# piezo-preamp-tickler_V0-9b.net
KiCad netlist of a schematic drawn in EAGLE
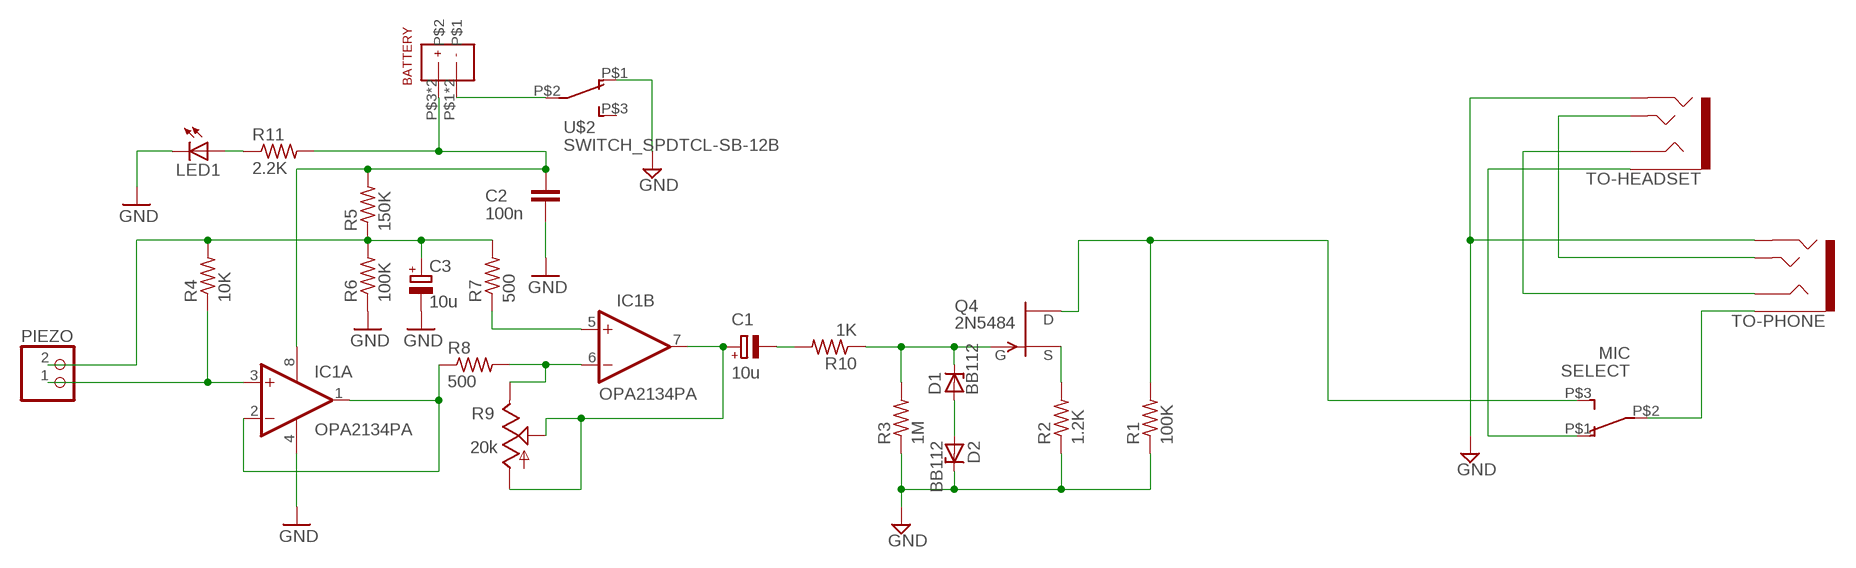
[diagram p0: schematic, sheet 1]

(export (version "E")
  (design (tool "Eeschema 10.0.6"))
  (components
    (comp (ref "BATTERY")
      (value "BATTERY-A27")
      (footprint "eagle-import:BATTERY-A27-KEYSTONE-3651")
      (libsource (lib "eagle-import") (part "BATTERY-A27"))
    )
    (comp (ref "C1")
      (value "10u")
      (footprint "eagle-import:TT2D5L")
      (libsource (lib "eagle-import") (part "CPOL-EUTT2D5L"))
    )
    (comp (ref "C2")
      (value "100n")
      (footprint "eagle-import:C025-025X050")
      (libsource (lib "eagle-import") (part "C-EU025-025X050"))
    )
    (comp (ref "C3")
      (value "10u")
      (footprint "eagle-import:TT2D5L")
      (libsource (lib "eagle-import") (part "CPOL-EUTT2D5L"))
    )
    (comp (ref "D1")
      (value "BB112")
      (footprint "eagle-import:ZDIO-5")
      (libsource (lib "eagle-import") (part "ZENER-DIODEZD-5"))
    )
    (comp (ref "D2")
      (value "BB112")
      (footprint "eagle-import:ZDIO-5")
      (libsource (lib "eagle-import") (part "ZENER-DIODEZD-5"))
    )
    (comp (ref "IC1")
      (value "OPA2134PA")
      (footprint "eagle-import:DIL08")
      (libsource (lib "eagle-import") (part "OPA2PA134"))
    )
    (comp (ref "LED1")
      (value "LED3MM")
      (footprint "eagle-import:LED3MM")
      (libsource (lib "eagle-import") (part "LED3MM"))
    )
    (comp (ref "PIEZO")
      (value "JST_2PIN-THM")
      (footprint "eagle-import:JST-PH-2-THM")
      (libsource (lib "eagle-import") (part "JST_2PIN-THM"))
    )
    (comp (ref "Q4")
      (value "2N5484")
      (footprint "eagle-import:TO92-")
      (libsource (lib "eagle-import") (part "?5482N4"))
    )
    (comp (ref "R1")
      (value "100K")
      (footprint "eagle-import:0204_7")
      (libsource (lib "eagle-import") (part "R-US_0204/7"))
    )
    (comp (ref "R2")
      (value "1.2K")
      (footprint "eagle-import:0204_7")
      (libsource (lib "eagle-import") (part "R-US_0204/7"))
    )
    (comp (ref "R3")
      (value "1M")
      (footprint "eagle-import:0204_7")
      (libsource (lib "eagle-import") (part "R-US_0204/7"))
    )
    (comp (ref "R4")
      (value "10K")
      (footprint "eagle-import:0204_7")
      (libsource (lib "eagle-import") (part "R-US_0204/7"))
    )
    (comp (ref "R5")
      (value "150K")
      (footprint "eagle-import:0204_7")
      (libsource (lib "eagle-import") (part "R-US_0204/7"))
    )
    (comp (ref "R6")
      (value "100K")
      (footprint "eagle-import:0204_7")
      (libsource (lib "eagle-import") (part "R-US_0204/7"))
    )
    (comp (ref "R7")
      (value "500")
      (footprint "eagle-import:0204_7")
      (libsource (lib "eagle-import") (part "R-US_0204/7"))
    )
    (comp (ref "R8")
      (value "500")
      (footprint "eagle-import:0204_7")
      (libsource (lib "eagle-import") (part "R-US_0204/7"))
    )
    (comp (ref "R9")
      (value "20k")
      (footprint "eagle-import:TRIMPOT-BOURNS-3306F")
      (libsource (lib "eagle-import") (part "TRIMPOT-BOURNS"))
    )
    (comp (ref "R10")
      (value "1K")
      (footprint "eagle-import:0204_7")
      (libsource (lib "eagle-import") (part "R-US_0204/7"))
    )
    (comp (ref "R11")
      (value "2.2K")
      (footprint "eagle-import:0204_7")
      (libsource (lib "eagle-import") (part "R-US_0204/7"))
    )
    (comp (ref "SELECT")
      (value "MIC")
      (footprint "eagle-import:SWITCH_SPDT_CL-SB-12B")
      (libsource (lib "eagle-import") (part "SWITCH_SPDTCL-SB-12B"))
    )
    (comp (ref "TO-HEADSET")
      (value "AUDIO-JACK3LGPADS")
      (footprint "eagle-import:AUDIO-JACK-TRRS-SMD")
      (libsource (lib "eagle-import") (part "AUDIO-JACK3LGPADS"))
    )
    (comp (ref "TO-PHONE")
      (value "AUDIO-JACK3LGPADS")
      (footprint "eagle-import:AUDIO-JACK-TRRS-SMD")
      (libsource (lib "eagle-import") (part "AUDIO-JACK3LGPADS"))
    )
    (comp (ref "U$2")
      (value "SWITCH_SPDTCL-SB-12B")
      (footprint "eagle-import:SWITCH_SPDT_CL-SB-12B")
      (libsource (lib "eagle-import") (part "SWITCH_SPDTCL-SB-12B"))
    )
  )
  (nets
    (net (code "1") (name "GND") (class "Default")
      (node (ref "C2") (pin "1") (pinfunction "1_1") (pintype "passive"))
      (node (ref "C3") (pin "-") (pinfunction "-_-") (pintype "passive"))
      (node (ref "D2") (pin "C") (pinfunction "C_C") (pintype "passive"))
      (node (ref "IC1") (pin "4") (pinfunction "V-_4") (pintype "power_in"))
      (node (ref "LED1") (pin "K") (pinfunction "C_K") (pintype "passive"))
      (node (ref "R1") (pin "1") (pinfunction "1_1") (pintype "passive"))
      (node (ref "R2") (pin "1") (pinfunction "1_1") (pintype "passive"))
      (node (ref "R3") (pin "1") (pinfunction "1_1") (pintype "passive"))
      (node (ref "R6") (pin "1") (pinfunction "1_1") (pintype "passive"))
      (node (ref "TO-HEADSET") (pin "RING2") (pinfunction "RING2_RING2") (pintype "bidirectional"))
      (node (ref "TO-PHONE") (pin "RING2") (pinfunction "RING2_RING2") (pintype "bidirectional"))
      (node (ref "U$2") (pin "P$1") (pinfunction "1_P$1") (pintype "passive"))
    )
    (net (code "2") (name "Net-(C1-Pad-)") (class "Default")
      (node (ref "C1") (pin "-") (pinfunction "-_-") (pintype "passive"))
      (node (ref "R10") (pin "2") (pinfunction "2_2") (pintype "passive"))
    )
    (net (code "3") (name "Net-(D1-PadA)") (class "Default")
      (node (ref "D1") (pin "A") (pinfunction "A_A") (pintype "passive"))
      (node (ref "D2") (pin "A") (pinfunction "A_A") (pintype "passive"))
    )
    (net (code "4") (name "Net-(IC1A-+IN)") (class "Default")
      (node (ref "IC1") (pin "3") (pinfunction "+IN_3") (pintype "input"))
      (node (ref "PIEZO") (pin "1") (pinfunction "2_1") (pintype "passive"))
      (node (ref "R4") (pin "1") (pinfunction "1_1") (pintype "passive"))
    )
    (net (code "5") (name "Net-(IC1A--IN)") (class "Default")
      (node (ref "IC1") (pin "1") (pinfunction "OUT_1") (pintype "output"))
      (node (ref "IC1") (pin "2") (pinfunction "-IN_2") (pintype "input"))
      (node (ref "R8") (pin "1") (pinfunction "1_1") (pintype "passive"))
    )
    (net (code "6") (name "Net-(IC1A-V+)") (class "Default")
      (node (ref "BATTERY") (pin "P$3") (pinfunction "P$2_P$3") (pintype "bidirectional"))
      (node (ref "BATTERY") (pin "P$4") (pinfunction "P$2_P$4") (pintype "bidirectional"))
      (node (ref "C2") (pin "2") (pinfunction "2_2") (pintype "passive"))
      (node (ref "IC1") (pin "8") (pinfunction "V+_8") (pintype "power_in"))
      (node (ref "R11") (pin "2") (pinfunction "2_2") (pintype "passive"))
      (node (ref "R5") (pin "2") (pinfunction "2_2") (pintype "passive"))
    )
    (net (code "7") (name "Net-(IC1B-+IN)") (class "Default")
      (node (ref "IC1") (pin "5") (pinfunction "+IN_5") (pintype "input"))
      (node (ref "R7") (pin "1") (pinfunction "1_1") (pintype "passive"))
    )
    (net (code "8") (name "Net-(IC1B--IN)") (class "Default")
      (node (ref "IC1") (pin "6") (pinfunction "-IN_6") (pintype "input"))
      (node (ref "R8") (pin "2") (pinfunction "2_2") (pintype "passive"))
      (node (ref "R9") (pin "P$3") (pinfunction "OUT_P$3") (pintype "passive"))
    )
    (net (code "9") (name "Net-(IC1B-OUT)") (class "Default")
      (node (ref "C1") (pin "+") (pinfunction "+_+") (pintype "passive"))
      (node (ref "IC1") (pin "7") (pinfunction "OUT_7") (pintype "output"))
      (node (ref "R9") (pin "P$1") (pinfunction "IN_P$1") (pintype "passive"))
      (node (ref "R9") (pin "P$2") (pinfunction "WIPER_P$2") (pintype "passive"))
    )
    (net (code "10") (name "Net-(LED1-PadA)") (class "Default")
      (node (ref "LED1") (pin "A") (pinfunction "A_A") (pintype "passive"))
      (node (ref "R11") (pin "1") (pinfunction "1_1") (pintype "passive"))
    )
    (net (code "11") (name "Net-(PIEZO-1)") (class "Default")
      (node (ref "C3") (pin "+") (pinfunction "+_+") (pintype "passive"))
      (node (ref "PIEZO") (pin "2") (pinfunction "1_2") (pintype "passive"))
      (node (ref "R4") (pin "2") (pinfunction "2_2") (pintype "passive"))
      (node (ref "R5") (pin "1") (pinfunction "1_1") (pintype "passive"))
      (node (ref "R6") (pin "2") (pinfunction "2_2") (pintype "passive"))
      (node (ref "R7") (pin "2") (pinfunction "2_2") (pintype "passive"))
    )
    (net (code "12") (name "Net-(Q4-D)") (class "Default")
      (node (ref "Q4") (pin "3") (pinfunction "D_3") (pintype "passive"))
      (node (ref "R1") (pin "2") (pinfunction "2_2") (pintype "passive"))
      (node (ref "SELECT") (pin "P$3") (pinfunction "3_P$3") (pintype "passive"))
    )
    (net (code "13") (name "Net-(Q4-G)") (class "Default")
      (node (ref "D1") (pin "C") (pinfunction "C_C") (pintype "passive"))
      (node (ref "Q4") (pin "1") (pinfunction "G_1") (pintype "passive"))
      (node (ref "R10") (pin "1") (pinfunction "1_1") (pintype "passive"))
      (node (ref "R3") (pin "2") (pinfunction "2_2") (pintype "passive"))
    )
    (net (code "14") (name "Net-(Q4-S)") (class "Default")
      (node (ref "Q4") (pin "2") (pinfunction "S_2") (pintype "passive"))
      (node (ref "R2") (pin "2") (pinfunction "2_2") (pintype "passive"))
    )
    (net (code "15") (name "Net-(SELECT-1)") (class "Default")
      (node (ref "SELECT") (pin "P$1") (pinfunction "1_P$1") (pintype "passive"))
      (node (ref "TO-HEADSET") (pin "EARTH") (pinfunction "EARTH_EARTH") (pintype "bidirectional"))
    )
    (net (code "16") (name "Net-(SELECT-2)") (class "Default")
      (node (ref "SELECT") (pin "P$2") (pinfunction "2_P$2") (pintype "passive"))
      (node (ref "TO-PHONE") (pin "EARTH") (pinfunction "EARTH_EARTH") (pintype "bidirectional"))
    )
    (net (code "17") (name "Net-(TO-HEADSET-PadRING1)") (class "Default")
      (node (ref "TO-HEADSET") (pin "RING1") (pinfunction "RING1_RING1") (pintype "bidirectional"))
      (node (ref "TO-PHONE") (pin "RING1") (pinfunction "RING1_RING1") (pintype "bidirectional"))
    )
    (net (code "18") (name "Net-(TO-HEADSET-PadTIP)") (class "Default")
      (node (ref "TO-HEADSET") (pin "TIP") (pinfunction "TIP_TIP") (pintype "bidirectional"))
      (node (ref "TO-PHONE") (pin "TIP") (pinfunction "TIP_TIP") (pintype "bidirectional"))
    )
    (net (code "19") (name "Net-(U$2-2)") (class "Default")
      (node (ref "BATTERY") (pin "P$1") (pinfunction "P$1_P$1") (pintype "bidirectional"))
      (node (ref "BATTERY") (pin "P$2") (pinfunction "P$1_P$2") (pintype "bidirectional"))
      (node (ref "U$2") (pin "P$2") (pinfunction "2_P$2") (pintype "passive"))
    )
    (net (code "20") (name "unconnected-(U$2-3-PadP$3)") (class "Default")
      (node (ref "U$2") (pin "P$3") (pinfunction "3_P$3") (pintype "passive"))
    )
  )
)
